# SpsctrumCharacteristicTester.net
KiCad netlist of a schematic drawn in Altium Designer
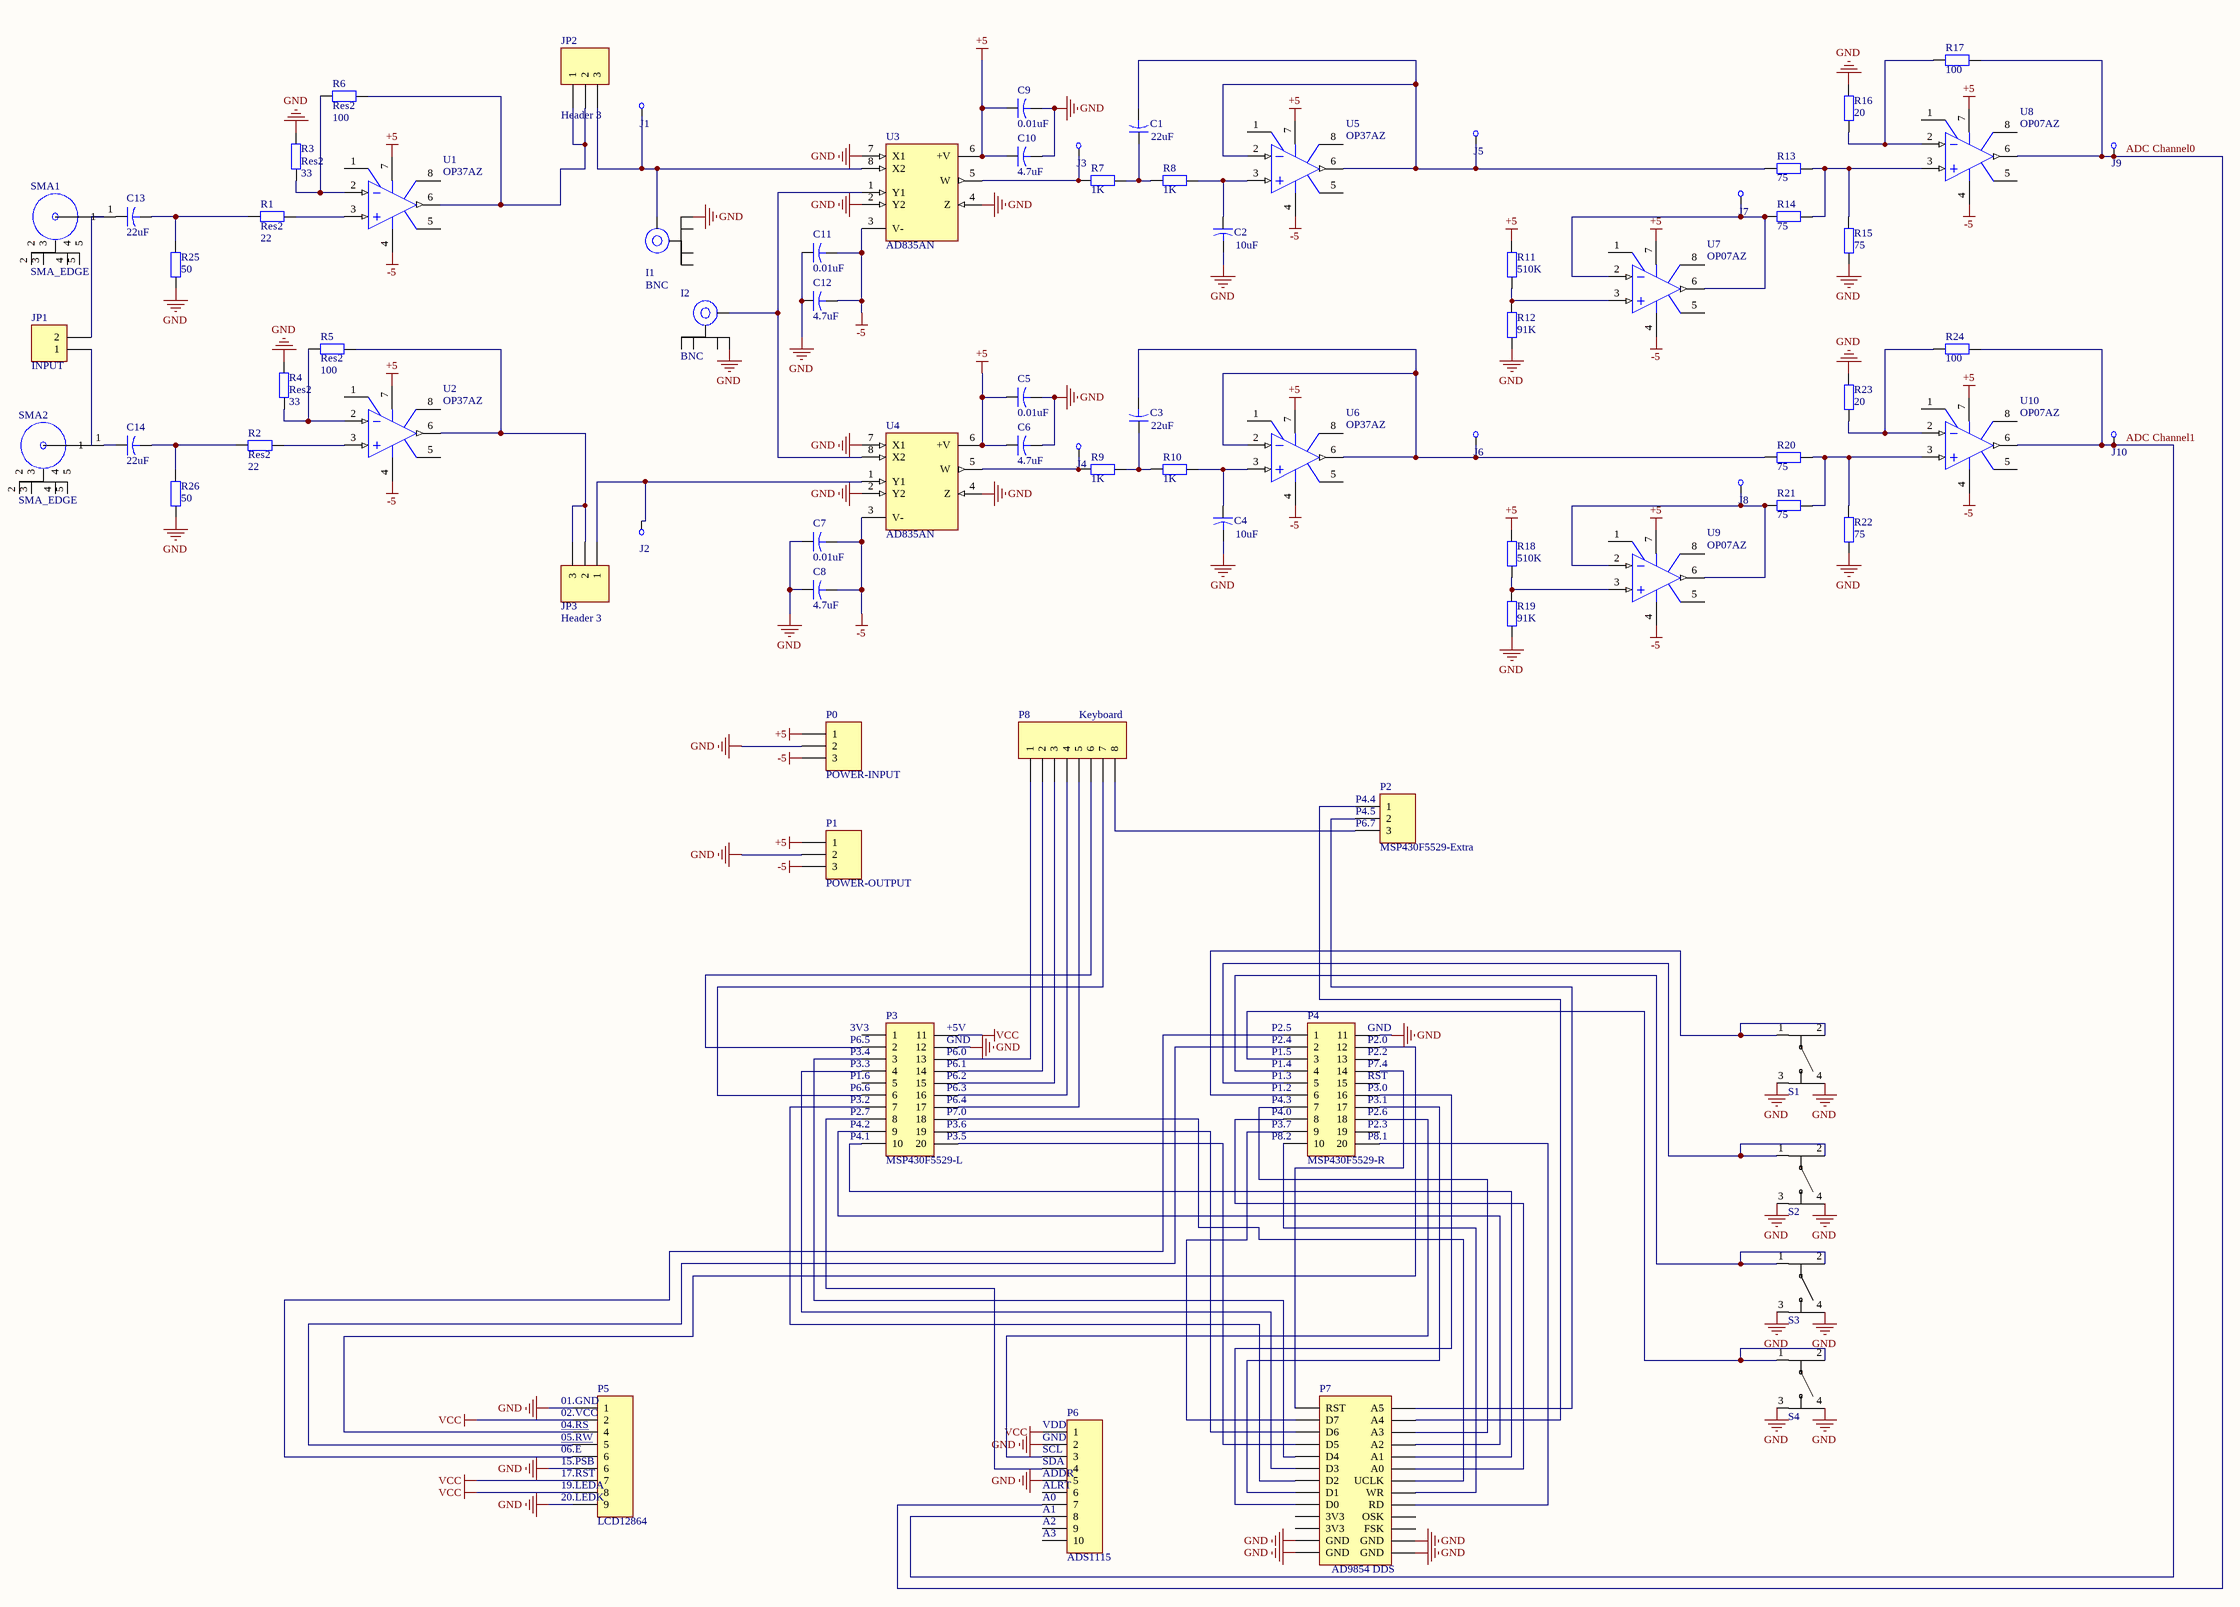
[diagram p0: SpsctrumCharacteristicTester.SchDoc]

(export (version "E")
  (design (tool "Eeschema 10.0.6"))
  (components
    (comp (ref "C1")
      (value "22uF")
      (footprint "CAPR5-4X5")
      (description "Capacitor")
      (fields (field (name "Comment") "Cap2") (field (name "PUBLISHER") "Altium Limited"))
      (libsource (lib "Miscellaneous Devices") (part "Cap2"))
    )
    (comp (ref "C2")
      (value "10uF")
      (footprint "CAPR5-4X5")
      (description "Capacitor")
      (fields (field (name "Comment") "Cap2") (field (name "PUBLISHER") "Altium Limited"))
      (libsource (lib "Miscellaneous Devices") (part "Cap2"))
    )
    (comp (ref "C3")
      (value "22uF")
      (footprint "CAPR5-4X5")
      (description "Capacitor")
      (fields (field (name "Comment") "Cap2") (field (name "PUBLISHER") "Altium Limited"))
      (libsource (lib "Miscellaneous Devices") (part "Cap2"))
    )
    (comp (ref "C4")
      (value "10uF")
      (footprint "CAPR5-4X5")
      (description "Capacitor")
      (fields (field (name "Comment") "Cap2") (field (name "PUBLISHER") "Altium Limited"))
      (libsource (lib "Miscellaneous Devices") (part "Cap2"))
    )
    (comp (ref "C5")
      (value "0.01uF")
      (footprint "CAPR5-4X5")
      (description "Capacitor")
      (fields (field (name "Comment") "Cap2") (field (name "PUBLISHER") "Altium Limited"))
      (libsource (lib "Miscellaneous Devices") (part "Cap2"))
    )
    (comp (ref "C6")
      (value "4.7uF")
      (footprint "CAPR5-4X5")
      (description "Capacitor")
      (fields (field (name "Comment") "Cap2") (field (name "PUBLISHER") "Altium Limited"))
      (libsource (lib "Miscellaneous Devices") (part "Cap2"))
    )
    (comp (ref "C7")
      (value "0.01uF")
      (footprint "CAPR5-4X5")
      (description "Capacitor")
      (fields (field (name "Comment") "Cap2") (field (name "PUBLISHER") "Altium Limited"))
      (libsource (lib "Miscellaneous Devices") (part "Cap2"))
    )
    (comp (ref "C8")
      (value "4.7uF")
      (footprint "CAPR5-4X5")
      (description "Capacitor")
      (fields (field (name "Comment") "Cap2") (field (name "PUBLISHER") "Altium Limited"))
      (libsource (lib "Miscellaneous Devices") (part "Cap2"))
    )
    (comp (ref "C9")
      (value "0.01uF")
      (footprint "CAPR5-4X5")
      (description "Capacitor")
      (fields (field (name "Comment") "Cap2") (field (name "PUBLISHER") "Altium Limited"))
      (libsource (lib "Miscellaneous Devices") (part "Cap2"))
    )
    (comp (ref "C10")
      (value "4.7uF")
      (footprint "CAPR5-4X5")
      (description "Capacitor")
      (fields (field (name "Comment") "Cap2") (field (name "PUBLISHER") "Altium Limited"))
      (libsource (lib "Miscellaneous Devices") (part "Cap2"))
    )
    (comp (ref "C11")
      (value "0.01uF")
      (footprint "CAPR5-4X5")
      (description "Capacitor")
      (fields (field (name "Comment") "Cap2") (field (name "PUBLISHER") "Altium Limited"))
      (libsource (lib "Miscellaneous Devices") (part "Cap2"))
    )
    (comp (ref "C12")
      (value "4.7uF")
      (footprint "CAPR5-4X5")
      (description "Capacitor")
      (fields (field (name "Comment") "Cap2") (field (name "PUBLISHER") "Altium Limited"))
      (libsource (lib "Miscellaneous Devices") (part "Cap2"))
    )
    (comp (ref "C13")
      (value "22uF")
      (footprint "CAPR5-4X5")
      (description "Capacitor")
      (fields (field (name "Comment") "Cap2") (field (name "PUBLISHER") "Altium Limited"))
      (libsource (lib "Miscellaneous Devices") (part "Cap2"))
    )
    (comp (ref "C14")
      (value "22uF")
      (footprint "CAPR5-4X5")
      (description "Capacitor")
      (fields (field (name "Comment") "Cap2") (field (name "PUBLISHER") "Altium Limited"))
      (libsource (lib "Miscellaneous Devices") (part "Cap2"))
    )
    (comp (ref "I1") (value "BNC") (footprint "BNC-KWE") (libsource (lib "BNC") (part "BNC")))
    (comp (ref "I2") (value "BNC") (footprint "BNC-KWE") (libsource (lib "BNC") (part "BNC")))
    (comp (ref "J1")
      (value "CHECK")
      (footprint "CHECK-A")
      (description "测试点")
      (libsource (lib "0MyLib") (part "CHECK"))
    )
    (comp (ref "J2")
      (value "CHECK")
      (footprint "CHECK-A")
      (description "测试点")
      (libsource (lib "0MyLib") (part "CHECK"))
    )
    (comp (ref "J3")
      (value "CHECK")
      (footprint "CHECK-A")
      (description "测试点")
      (libsource (lib "0MyLib") (part "CHECK"))
    )
    (comp (ref "J4")
      (value "CHECK")
      (footprint "CHECK-A")
      (description "测试点")
      (libsource (lib "0MyLib") (part "CHECK"))
    )
    (comp (ref "J5")
      (value "CHECK")
      (footprint "CHECK-A")
      (description "测试点")
      (libsource (lib "0MyLib") (part "CHECK"))
    )
    (comp (ref "J6")
      (value "CHECK")
      (footprint "CHECK-A")
      (description "测试点")
      (libsource (lib "0MyLib") (part "CHECK"))
    )
    (comp (ref "J7")
      (value "CHECK")
      (footprint "CHECK-A")
      (description "测试点")
      (libsource (lib "0MyLib") (part "CHECK"))
    )
    (comp (ref "J8")
      (value "CHECK")
      (footprint "CHECK-A")
      (description "测试点")
      (libsource (lib "0MyLib") (part "CHECK"))
    )
    (comp (ref "J9")
      (value "CHECK")
      (footprint "CHECK-A")
      (description "测试点")
      (libsource (lib "0MyLib") (part "CHECK"))
    )
    (comp (ref "J10")
      (value "CHECK")
      (footprint "CHECK-A")
      (description "测试点")
      (libsource (lib "0MyLib") (part "CHECK"))
    )
    (comp (ref "JP1")
      (value "INPUT")
      (footprint "HDR1X2")
      (description "Header, 2-Pin")
      (fields (field (name "PUBLISHER") "Altium Limited"))
      (libsource (lib "Miscellaneous Connectors") (part "Header 2"))
    )
    (comp (ref "JP2")
      (value "Header 3")
      (footprint "HDR1X3")
      (description "Header, 3-Pin")
      (fields (field (name "PUBLISHER") "Altium Limited"))
      (libsource (lib "") (part "Header 3_1"))
    )
    (comp (ref "JP3")
      (value "Header 3")
      (footprint "HDR1X3")
      (description "Header, 3-Pin")
      (fields (field (name "PUBLISHER") "Altium Limited"))
      (libsource (lib "") (part "Header 3_2"))
    )
    (comp (ref "P0")
      (value "POWER-INPUT")
      (footprint "HDR1X3")
      (description "Header, 3-Pin")
      (fields (field (name "PUBLISHER") "Altium Limited"))
      (libsource (lib "Miscellaneous Connectors") (part "Header 3"))
    )
    (comp (ref "P1")
      (value "POWER-OUTPUT")
      (footprint "HDR1X3")
      (description "Header, 3-Pin")
      (fields (field (name "PUBLISHER") "Altium Limited"))
      (libsource (lib "Miscellaneous Connectors") (part "Header 3"))
    )
    (comp (ref "P2")
      (value "MSP430F5529-Extra")
      (footprint "HDR1X3")
      (description "Header, 3-Pin")
      (fields (field (name "PUBLISHER") "Altium Limited"))
      (libsource (lib "Miscellaneous Connectors") (part "Header 3"))
    )
    (comp (ref "P3")
      (value "MSP430F5529-L")
      (footprint "HDR2X10_CEN")
      (description "Header, 10-Pin, Dual row")
      (fields (field (name "PUBLISHER") "Altium Limited"))
      (libsource (lib "Miscellaneous Connectors") (part "Header 10X2A"))
    )
    (comp (ref "P4")
      (value "MSP430F5529-R")
      (footprint "HDR2X10_CEN")
      (description "Header, 10-Pin, Dual row")
      (fields (field (name "PUBLISHER") "Altium Limited"))
      (libsource (lib "Miscellaneous Connectors") (part "Header 10X2A"))
    )
    (comp (ref "P5")
      (value "LCD12864")
      (footprint "HDR1X9")
      (description "Header, 9-Pin")
      (fields (field (name "PUBLISHER") "Altium Limited"))
      (libsource (lib "Miscellaneous Connectors") (part "Header 9"))
    )
    (comp (ref "P6")
      (value "ADS1115")
      (footprint "HDR1X10")
      (description "Header, 10-Pin")
      (fields (field (name "PUBLISHER") "Altium Limited"))
      (libsource (lib "Miscellaneous Connectors") (part "Header 10"))
    )
    (comp (ref "P7")
      (value "~")
      (footprint "IDC-26")
      (libsource (lib "AD9854 Connector") (part "AD9854 DDS"))
    )
    (comp (ref "P8")
      (value "Keyboard")
      (footprint "HDR1X8")
      (description "Header, 8-Pin")
      (fields (field (name "PUBLISHER") "Altium Limited"))
      (libsource (lib "Miscellaneous Connectors") (part "Header 8"))
    )
    (comp (ref "R1")
      (value "Res2")
      (footprint "AXIAL-0.4")
      (description "Resistor")
      (fields (field (name "ALTIUM_VALUE") "22") (field (name "PUBLISHER") "Altium Limited"))
      (libsource (lib "") (part "Res2_1"))
    )
    (comp (ref "R2")
      (value "Res2")
      (footprint "AXIAL-0.4")
      (description "Resistor")
      (fields (field (name "ALTIUM_VALUE") "22") (field (name "PUBLISHER") "Altium Limited"))
      (libsource (lib "") (part "Res2_1"))
    )
    (comp (ref "R3")
      (value "Res2")
      (footprint "AXIAL-0.4")
      (description "Resistor")
      (fields (field (name "ALTIUM_VALUE") "33") (field (name "PUBLISHER") "Altium Limited"))
      (libsource (lib "Miscellaneous Devices") (part "Res2"))
    )
    (comp (ref "R4")
      (value "Res2")
      (footprint "AXIAL-0.4")
      (description "Resistor")
      (fields (field (name "ALTIUM_VALUE") "33") (field (name "PUBLISHER") "Altium Limited"))
      (libsource (lib "Miscellaneous Devices") (part "Res2"))
    )
    (comp (ref "R5")
      (value "Res2")
      (footprint "AXIAL-0.4")
      (description "Resistor")
      (fields (field (name "ALTIUM_VALUE") "100") (field (name "PUBLISHER") "Altium Limited"))
      (libsource (lib "") (part "Res2_2"))
    )
    (comp (ref "R6")
      (value "Res2")
      (footprint "AXIAL-0.4")
      (description "Resistor")
      (fields (field (name "ALTIUM_VALUE") "100") (field (name "PUBLISHER") "Altium Limited"))
      (libsource (lib "") (part "Res2_2"))
    )
    (comp (ref "R7")
      (value "1K")
      (footprint "AXIAL-0.4")
      (description "Resistor")
      (fields (field (name "Comment") "Res2") (field (name "PUBLISHER") "Altium Limited"))
      (libsource (lib "") (part "Res2_1"))
    )
    (comp (ref "R8")
      (value "1K")
      (footprint "AXIAL-0.4")
      (description "Resistor")
      (fields (field (name "Comment") "Res2") (field (name "PUBLISHER") "Altium Limited"))
      (libsource (lib "") (part "Res2_1"))
    )
    (comp (ref "R9")
      (value "1K")
      (footprint "AXIAL-0.4")
      (description "Resistor")
      (fields (field (name "Comment") "Res2") (field (name "PUBLISHER") "Altium Limited"))
      (libsource (lib "") (part "Res2_1"))
    )
    (comp (ref "R10")
      (value "1K")
      (footprint "AXIAL-0.4")
      (description "Resistor")
      (fields (field (name "Comment") "Res2") (field (name "PUBLISHER") "Altium Limited"))
      (libsource (lib "") (part "Res2_1"))
    )
    (comp (ref "R11")
      (value "510K")
      (footprint "AXIAL-0.4")
      (description "Resistor")
      (fields (field (name "Comment") "Res2") (field (name "PUBLISHER") "Altium Limited"))
      (libsource (lib "Miscellaneous Devices") (part "Res2"))
    )
    (comp (ref "R12")
      (value "91K")
      (footprint "AXIAL-0.4")
      (description "Resistor")
      (fields (field (name "Comment") "Res2") (field (name "PUBLISHER") "Altium Limited"))
      (libsource (lib "Miscellaneous Devices") (part "Res2"))
    )
    (comp (ref "R13")
      (value "75")
      (footprint "AXIAL-0.4")
      (description "Resistor")
      (fields (field (name "Comment") "Res2") (field (name "PUBLISHER") "Altium Limited"))
      (libsource (lib "") (part "Res2_1"))
    )
    (comp (ref "R14")
      (value "75")
      (footprint "AXIAL-0.4")
      (description "Resistor")
      (fields (field (name "Comment") "Res2") (field (name "PUBLISHER") "Altium Limited"))
      (libsource (lib "") (part "Res2_1"))
    )
    (comp (ref "R15")
      (value "75")
      (footprint "AXIAL-0.4")
      (description "Resistor")
      (fields (field (name "Comment") "Res2") (field (name "PUBLISHER") "Altium Limited"))
      (libsource (lib "Miscellaneous Devices") (part "Res2"))
    )
    (comp (ref "R16")
      (value "20")
      (footprint "AXIAL-0.4")
      (description "Resistor")
      (fields (field (name "Comment") "Res2") (field (name "PUBLISHER") "Altium Limited"))
      (libsource (lib "") (part "Res2_3"))
    )
    (comp (ref "R17")
      (value "100")
      (footprint "AXIAL-0.4")
      (description "Resistor")
      (fields (field (name "Comment") "Res2") (field (name "PUBLISHER") "Altium Limited"))
      (libsource (lib "") (part "Res2_1"))
    )
    (comp (ref "R18")
      (value "510K")
      (footprint "AXIAL-0.4")
      (description "Resistor")
      (fields (field (name "Comment") "Res2") (field (name "PUBLISHER") "Altium Limited"))
      (libsource (lib "Miscellaneous Devices") (part "Res2"))
    )
    (comp (ref "R19")
      (value "91K")
      (footprint "AXIAL-0.4")
      (description "Resistor")
      (fields (field (name "Comment") "Res2") (field (name "PUBLISHER") "Altium Limited"))
      (libsource (lib "Miscellaneous Devices") (part "Res2"))
    )
    (comp (ref "R20")
      (value "75")
      (footprint "AXIAL-0.4")
      (description "Resistor")
      (fields (field (name "Comment") "Res2") (field (name "PUBLISHER") "Altium Limited"))
      (libsource (lib "") (part "Res2_1"))
    )
    (comp (ref "R21")
      (value "75")
      (footprint "AXIAL-0.4")
      (description "Resistor")
      (fields (field (name "Comment") "Res2") (field (name "PUBLISHER") "Altium Limited"))
      (libsource (lib "") (part "Res2_1"))
    )
    (comp (ref "R22")
      (value "75")
      (footprint "AXIAL-0.4")
      (description "Resistor")
      (fields (field (name "Comment") "Res2") (field (name "PUBLISHER") "Altium Limited"))
      (libsource (lib "Miscellaneous Devices") (part "Res2"))
    )
    (comp (ref "R23")
      (value "20")
      (footprint "AXIAL-0.4")
      (description "Resistor")
      (fields (field (name "Comment") "Res2") (field (name "PUBLISHER") "Altium Limited"))
      (libsource (lib "") (part "Res2_3"))
    )
    (comp (ref "R24")
      (value "100")
      (footprint "AXIAL-0.4")
      (description "Resistor")
      (fields (field (name "Comment") "Res2") (field (name "PUBLISHER") "Altium Limited"))
      (libsource (lib "") (part "Res2_1"))
    )
    (comp (ref "R25")
      (value "50")
      (footprint "AXIAL-0.4")
      (description "Resistor")
      (fields (field (name "Comment") "Res2") (field (name "PUBLISHER") "Altium Limited"))
      (libsource (lib "Miscellaneous Devices") (part "Res2"))
    )
    (comp (ref "R26")
      (value "50")
      (footprint "AXIAL-0.4")
      (description "Resistor")
      (fields (field (name "Comment") "Res2") (field (name "PUBLISHER") "Altium Limited"))
      (libsource (lib "Miscellaneous Devices") (part "Res2"))
    )
    (comp (ref "S1") (value "6*6 微动开关") (footprint "6*6微动开关") (libsource (lib "Siwitches") (part "6*6 微动开关")))
    (comp (ref "S2") (value "6*6 微动开关") (footprint "6*6微动开关") (libsource (lib "Siwitches") (part "6*6 微动开关")))
    (comp (ref "S3") (value "6*6 微动开关") (footprint "6*6微动开关") (libsource (lib "Siwitches") (part "6*6 微动开关")))
    (comp (ref "S4") (value "6*6 微动开关") (footprint "6*6微动开关") (libsource (lib "Siwitches") (part "6*6 微动开关")))
    (comp (ref "SMA1")
      (value "SMA_EDGE")
      (footprint "SMA_EDGE")
      (description "SMA接口")
      (libsource (lib "SMA") (part "SMA_EDGE"))
    )
    (comp (ref "SMA2")
      (value "SMA_EDGE")
      (footprint "SMA_EDGE")
      (description "SMA接口")
      (libsource (lib "SMA") (part "SMA_EDGE"))
    )
    (comp (ref "U1")
      (value "OP37AZ")
      (footprint "Q-8")
      (description "Low-Noise, Precision, High-Speed Operational Amplifier (Avcl >= 5)")
      (fields (field (name "PUBLISHER") "Altium Limited"))
      (libsource (lib "AD Operational Amplifier") (part "OP37AZ"))
    )
    (comp (ref "U2")
      (value "OP37AZ")
      (footprint "Q-8")
      (description "Low-Noise, Precision, High-Speed Operational Amplifier (Avcl >= 5)")
      (fields (field (name "PUBLISHER") "Altium Limited"))
      (libsource (lib "AD Operational Amplifier") (part "OP37AZ"))
    )
    (comp (ref "U3")
      (value "AD835AN")
      (footprint "N-8_A")
      (description "250MHz, Voltage Output 4-Quadrant Multiplier")
      (fields (field (name "PUBLISHER") "Altium Limited"))
      (libsource (lib "AD Analog Multiplier Divider") (part "AD835AN"))
    )
    (comp (ref "U4")
      (value "AD835AN")
      (footprint "N-8_A")
      (description "250MHz, Voltage Output 4-Quadrant Multiplier")
      (fields (field (name "PUBLISHER") "Altium Limited"))
      (libsource (lib "AD Analog Multiplier Divider") (part "AD835AN"))
    )
    (comp (ref "U5")
      (value "OP37AZ")
      (footprint "Q-8")
      (description "Low-Noise, Precision, High-Speed Operational Amplifier (Avcl >= 5)")
      (fields (field (name "PUBLISHER") "Altium Limited"))
      (libsource (lib "AD Operational Amplifier") (part "OP37AZ"))
    )
    (comp (ref "U6")
      (value "OP37AZ")
      (footprint "Q-8")
      (description "Low-Noise, Precision, High-Speed Operational Amplifier (Avcl >= 5)")
      (fields (field (name "PUBLISHER") "Altium Limited"))
      (libsource (lib "AD Operational Amplifier") (part "OP37AZ"))
    )
    (comp (ref "U7")
      (value "OP07AZ")
      (footprint "Q-8")
      (description "Ultra-Low Offset Voltage Operational Amplifier")
      (fields (field (name "PUBLISHER") "Altium Limited"))
      (libsource (lib "AD Operational Amplifier") (part "OP07AZ"))
    )
    (comp (ref "U8")
      (value "OP07AZ")
      (footprint "Q-8")
      (description "Ultra-Low Offset Voltage Operational Amplifier")
      (fields (field (name "PUBLISHER") "Altium Limited"))
      (libsource (lib "AD Operational Amplifier") (part "OP07AZ"))
    )
    (comp (ref "U9")
      (value "OP07AZ")
      (footprint "Q-8")
      (description "Ultra-Low Offset Voltage Operational Amplifier")
      (fields (field (name "PUBLISHER") "Altium Limited"))
      (libsource (lib "AD Operational Amplifier") (part "OP07AZ"))
    )
    (comp (ref "U10")
      (value "OP07AZ")
      (footprint "Q-8")
      (description "Ultra-Low Offset Voltage Operational Amplifier")
      (fields (field (name "PUBLISHER") "Altium Limited"))
      (libsource (lib "AD Operational Amplifier") (part "OP07AZ"))
    )
  )
  (nets
    (net (code "1") (name "+5") (class "Default")
      (node (ref "C10") (pin "1") (pinfunction "1_1") (pintype "passive"))
      (node (ref "C5") (pin "1") (pinfunction "1_1") (pintype "passive"))
      (node (ref "C6") (pin "1") (pinfunction "1_1") (pintype "passive"))
      (node (ref "C9") (pin "1") (pinfunction "1_1") (pintype "passive"))
      (node (ref "P0") (pin "1") (pinfunction "1_1") (pintype "passive"))
      (node (ref "P1") (pin "1") (pinfunction "1_1") (pintype "passive"))
      (node (ref "R11") (pin "2") (pinfunction "2_2") (pintype "passive"))
      (node (ref "R18") (pin "2") (pinfunction "2_2") (pintype "passive"))
      (node (ref "U1") (pin "7") (pinfunction "V+_7") (pintype "power_in"))
      (node (ref "U10") (pin "7") (pinfunction "V+_7") (pintype "power_in"))
      (node (ref "U2") (pin "7") (pinfunction "V+_7") (pintype "power_in"))
      (node (ref "U3") (pin "6") (pinfunction "+V_6") (pintype "power_in"))
      (node (ref "U4") (pin "6") (pinfunction "+V_6") (pintype "power_in"))
      (node (ref "U5") (pin "7") (pinfunction "V+_7") (pintype "power_in"))
      (node (ref "U6") (pin "7") (pinfunction "V+_7") (pintype "power_in"))
      (node (ref "U7") (pin "7") (pinfunction "V+_7") (pintype "power_in"))
      (node (ref "U8") (pin "7") (pinfunction "V+_7") (pintype "power_in"))
      (node (ref "U9") (pin "7") (pinfunction "V+_7") (pintype "power_in"))
    )
    (net (code "2") (name "-5") (class "Default")
      (node (ref "C11") (pin "2") (pinfunction "2_2") (pintype "passive"))
      (node (ref "C12") (pin "2") (pinfunction "2_2") (pintype "passive"))
      (node (ref "C7") (pin "2") (pinfunction "2_2") (pintype "passive"))
      (node (ref "C8") (pin "2") (pinfunction "2_2") (pintype "passive"))
      (node (ref "P0") (pin "3") (pinfunction "3_3") (pintype "passive"))
      (node (ref "P1") (pin "3") (pinfunction "3_3") (pintype "passive"))
      (node (ref "U1") (pin "4") (pinfunction "V-_4") (pintype "power_in"))
      (node (ref "U10") (pin "4") (pinfunction "V-_4") (pintype "power_in"))
      (node (ref "U2") (pin "4") (pinfunction "V-_4") (pintype "power_in"))
      (node (ref "U3") (pin "3") (pinfunction "V-_3") (pintype "power_in"))
      (node (ref "U4") (pin "3") (pinfunction "V-_3") (pintype "power_in"))
      (node (ref "U5") (pin "4") (pinfunction "V-_4") (pintype "power_in"))
      (node (ref "U6") (pin "4") (pinfunction "V-_4") (pintype "power_in"))
      (node (ref "U7") (pin "4") (pinfunction "V-_4") (pintype "power_in"))
      (node (ref "U8") (pin "4") (pinfunction "V-_4") (pintype "power_in"))
      (node (ref "U9") (pin "4") (pinfunction "V-_4") (pintype "power_in"))
    )
    (net (code "3") (name "/ADC Channel0") (class "Default")
      (node (ref "J9") (pin "1") (pinfunction "1_1") (pintype "passive"))
      (node (ref "P6") (pin "7") (pinfunction "7_7") (pintype "passive"))
      (node (ref "R17") (pin "2") (pinfunction "2_2") (pintype "passive"))
      (node (ref "U8") (pin "6") (pinfunction "OUT_6") (pintype "output"))
    )
    (net (code "4") (name "/ADC Channel1") (class "Default")
      (node (ref "J10") (pin "1") (pinfunction "1_1") (pintype "passive"))
      (node (ref "P6") (pin "8") (pinfunction "8_8") (pintype "passive"))
      (node (ref "R24") (pin "2") (pinfunction "2_2") (pintype "passive"))
      (node (ref "U10") (pin "6") (pinfunction "OUT_6") (pintype "output"))
    )
    (net (code "5") (name "GND") (class "Default")
      (node (ref "C10") (pin "2") (pinfunction "2_2") (pintype "passive"))
      (node (ref "C11") (pin "1") (pinfunction "1_1") (pintype "passive"))
      (node (ref "C12") (pin "1") (pinfunction "1_1") (pintype "passive"))
      (node (ref "C2") (pin "2") (pinfunction "2_2") (pintype "passive"))
      (node (ref "C4") (pin "2") (pinfunction "2_2") (pintype "passive"))
      (node (ref "C5") (pin "2") (pinfunction "2_2") (pintype "passive"))
      (node (ref "C6") (pin "2") (pinfunction "2_2") (pintype "passive"))
      (node (ref "C7") (pin "1") (pinfunction "1_1") (pintype "passive"))
      (node (ref "C8") (pin "1") (pinfunction "1_1") (pintype "passive"))
      (node (ref "C9") (pin "2") (pinfunction "2_2") (pintype "passive"))
      (node (ref "I1") (pin "5") (pinfunction "5_5") (pintype "passive"))
      (node (ref "I2") (pin "5") (pinfunction "5_5") (pintype "passive"))
      (node (ref "P0") (pin "2") (pinfunction "2_2") (pintype "passive"))
      (node (ref "P1") (pin "2") (pinfunction "2_2") (pintype "passive"))
      (node (ref "P3") (pin "12") (pinfunction "12_12") (pintype "passive"))
      (node (ref "P4") (pin "11") (pinfunction "11_11") (pintype "passive"))
      (node (ref "P5") (pin "1") (pinfunction "1_1") (pintype "passive"))
      (node (ref "P5") (pin "6") (pinfunction "6_6") (pintype "passive"))
      (node (ref "P5") (pin "9") (pinfunction "9_9") (pintype "passive"))
      (node (ref "P6") (pin "2") (pinfunction "2_2") (pintype "passive"))
      (node (ref "P6") (pin "5") (pinfunction "5_5") (pintype "passive"))
      (node (ref "P7") (pin "23") (pinfunction "GND_23") (pintype "passive"))
      (node (ref "P7") (pin "24") (pinfunction "GND_24") (pintype "passive"))
      (node (ref "P7") (pin "25") (pinfunction "GND_25") (pintype "passive"))
      (node (ref "P7") (pin "26") (pinfunction "GND_26") (pintype "passive"))
      (node (ref "R12") (pin "1") (pinfunction "1_1") (pintype "passive"))
      (node (ref "R15") (pin "1") (pinfunction "1_1") (pintype "passive"))
      (node (ref "R16") (pin "1") (pinfunction "1_1") (pintype "passive"))
      (node (ref "R19") (pin "1") (pinfunction "1_1") (pintype "passive"))
      (node (ref "R22") (pin "1") (pinfunction "1_1") (pintype "passive"))
      (node (ref "R23") (pin "1") (pinfunction "1_1") (pintype "passive"))
      (node (ref "R25") (pin "1") (pinfunction "1_1") (pintype "passive"))
      (node (ref "R26") (pin "1") (pinfunction "1_1") (pintype "passive"))
      (node (ref "R3") (pin "2") (pinfunction "2_2") (pintype "passive"))
      (node (ref "R4") (pin "2") (pinfunction "2_2") (pintype "passive"))
      (node (ref "S1") (pin "3") (pintype "passive"))
      (node (ref "S1") (pin "4") (pinfunction "4_4") (pintype "passive"))
      (node (ref "S2") (pin "3") (pintype "passive"))
      (node (ref "S2") (pin "4") (pinfunction "4_4") (pintype "passive"))
      (node (ref "S3") (pin "3") (pintype "passive"))
      (node (ref "S3") (pin "4") (pinfunction "4_4") (pintype "passive"))
      (node (ref "S4") (pin "3") (pintype "passive"))
      (node (ref "S4") (pin "4") (pinfunction "4_4") (pintype "passive"))
      (node (ref "U3") (pin "2") (pinfunction "Y2_2") (pintype "input"))
      (node (ref "U3") (pin "4") (pinfunction "Z_4") (pintype "input"))
      (node (ref "U3") (pin "7") (pinfunction "X1_7") (pintype "input"))
      (node (ref "U4") (pin "2") (pinfunction "Y2_2") (pintype "input"))
      (node (ref "U4") (pin "4") (pinfunction "Z_4") (pintype "input"))
      (node (ref "U4") (pin "7") (pinfunction "X1_7") (pintype "input"))
    )
    (net (code "6") (name "Net-(C1-Pad1)") (class "Default")
      (node (ref "C1") (pin "1") (pinfunction "1_1") (pintype "passive"))
      (node (ref "R7") (pin "2") (pinfunction "2_2") (pintype "passive"))
      (node (ref "R8") (pin "1") (pinfunction "1_1") (pintype "passive"))
    )
    (net (code "7") (name "Net-(C3-Pad1)") (class "Default")
      (node (ref "C3") (pin "1") (pinfunction "1_1") (pintype "passive"))
      (node (ref "R10") (pin "1") (pinfunction "1_1") (pintype "passive"))
      (node (ref "R9") (pin "2") (pinfunction "2_2") (pintype "passive"))
    )
    (net (code "8") (name "Net-(C13-Pad1)") (class "Default")
      (node (ref "C13") (pin "1") (pinfunction "1_1") (pintype "passive"))
      (node (ref "SMA1") (pin "1") (pinfunction "1_1") (pintype "passive"))
    )
    (net (code "9") (name "Net-(C13-Pad2)") (class "Default")
      (node (ref "C13") (pin "2") (pinfunction "2_2") (pintype "passive"))
      (node (ref "R1") (pin "1") (pinfunction "1_1") (pintype "passive"))
      (node (ref "R25") (pin "2") (pinfunction "2_2") (pintype "passive"))
    )
    (net (code "10") (name "Net-(C14-Pad1)") (class "Default")
      (node (ref "C14") (pin "1") (pinfunction "1_1") (pintype "passive"))
      (node (ref "SMA2") (pin "1") (pinfunction "1_1") (pintype "passive"))
    )
    (net (code "11") (name "Net-(C14-Pad2)") (class "Default")
      (node (ref "C14") (pin "2") (pinfunction "2_2") (pintype "passive"))
      (node (ref "R2") (pin "1") (pinfunction "1_1") (pintype "passive"))
      (node (ref "R26") (pin "2") (pinfunction "2_2") (pintype "passive"))
    )
    (net (code "12") (name "Net-(P2-Pad3)") (class "Default")
      (node (ref "P2") (pin "3") (pinfunction "3_3") (pintype "passive"))
      (node (ref "P8") (pin "8") (pinfunction "8_8") (pintype "passive"))
    )
    (net (code "13") (name "Net-(P3-Pad2)") (class "Default")
      (node (ref "P3") (pin "2") (pinfunction "2_2") (pintype "passive"))
      (node (ref "P8") (pin "6") (pinfunction "6_6") (pintype "passive"))
    )
    (net (code "14") (name "Net-(P3-Pad6)") (class "Default")
      (node (ref "P3") (pin "6") (pinfunction "6_6") (pintype "passive"))
      (node (ref "P8") (pin "7") (pinfunction "7_7") (pintype "passive"))
    )
    (net (code "15") (name "Net-(P3-Pad8)") (class "Default")
      (node (ref "P3") (pin "8") (pinfunction "8_8") (pintype "passive"))
      (node (ref "P6") (pin "4") (pinfunction "4_4") (pintype "passive"))
    )
    (net (code "16") (name "Net-(P3-Pad13)") (class "Default")
      (node (ref "P3") (pin "13") (pinfunction "13_13") (pintype "passive"))
      (node (ref "P8") (pin "1") (pinfunction "1_1") (pintype "passive"))
    )
    (net (code "17") (name "Net-(P3-Pad14)") (class "Default")
      (node (ref "P3") (pin "14") (pinfunction "14_14") (pintype "passive"))
      (node (ref "P8") (pin "2") (pinfunction "2_2") (pintype "passive"))
    )
    (net (code "18") (name "Net-(P3-Pad15)") (class "Default")
      (node (ref "P3") (pin "15") (pinfunction "15_15") (pintype "passive"))
      (node (ref "P8") (pin "3") (pinfunction "3_3") (pintype "passive"))
    )
    (net (code "19") (name "Net-(P3-Pad16)") (class "Default")
      (node (ref "P3") (pin "16") (pinfunction "16_16") (pintype "passive"))
      (node (ref "P8") (pin "4") (pinfunction "4_4") (pintype "passive"))
    )
    (net (code "20") (name "Net-(P3-Pad17)") (class "Default")
      (node (ref "P3") (pin "17") (pinfunction "17_17") (pintype "passive"))
      (node (ref "P8") (pin "5") (pinfunction "5_5") (pintype "passive"))
    )
    (net (code "21") (name "Net-(P4-Pad1)") (class "Default")
      (node (ref "P4") (pin "1") (pinfunction "1_1") (pintype "passive"))
      (node (ref "P5") (pin "6") (pinfunction "6_6") (pintype "passive"))
    )
    (net (code "22") (name "Net-(P4-Pad2)") (class "Default")
      (node (ref "P4") (pin "2") (pinfunction "2_2") (pintype "passive"))
      (node (ref "P5") (pin "5") (pinfunction "5_5") (pintype "passive"))
    )
    (net (code "23") (name "Net-(P4-Pad3)") (class "Default")
      (node (ref "P4") (pin "3") (pinfunction "3_3") (pintype "passive"))
      (node (ref "S4") (pin "1") (pinfunction "1_1") (pintype "passive"))
      (node (ref "S4") (pin "2") (pinfunction "2_2") (pintype "passive"))
    )
    (net (code "24") (name "Net-(P4-Pad4)") (class "Default")
      (node (ref "P4") (pin "4") (pinfunction "4_4") (pintype "passive"))
      (node (ref "S3") (pin "1") (pinfunction "1_1") (pintype "passive"))
      (node (ref "S3") (pin "2") (pinfunction "2_2") (pintype "passive"))
    )
    (net (code "25") (name "Net-(P4-Pad5)") (class "Default")
      (node (ref "P4") (pin "5") (pinfunction "5_5") (pintype "passive"))
      (node (ref "S2") (pin "1") (pinfunction "1_1") (pintype "passive"))
      (node (ref "S2") (pin "2") (pinfunction "2_2") (pintype "passive"))
    )
    (net (code "26") (name "Net-(P4-Pad6)") (class "Default")
      (node (ref "P4") (pin "6") (pinfunction "6_6") (pintype "passive"))
      (node (ref "S1") (pin "1") (pinfunction "1_1") (pintype "passive"))
      (node (ref "S1") (pin "2") (pinfunction "2_2") (pintype "passive"))
    )
    (net (code "27") (name "Net-(P4-Pad12)") (class "Default")
      (node (ref "P4") (pin "12") (pinfunction "12_12") (pintype "passive"))
      (node (ref "P5") (pin "4") (pinfunction "4_4") (pintype "passive"))
    )
    (net (code "28") (name "Net-(P4-Pad18)") (class "Default")
      (node (ref "P4") (pin "18") (pinfunction "18_18") (pintype "passive"))
      (node (ref "P6") (pin "3") (pinfunction "3_3") (pintype "passive"))
    )
    (net (code "29") (name "Net-(P7-A0)") (class "Default")
      (node (ref "P4") (pin "8") (pinfunction "8_8") (pintype "passive"))
      (node (ref "P7") (pin "12") (pinfunction "A0_12") (pintype "passive"))
    )
    (net (code "30") (name "Net-(P7-A1)") (class "Default")
      (node (ref "P3") (pin "10") (pinfunction "10_10") (pintype "passive"))
      (node (ref "P7") (pin "10") (pinfunction "A1_10") (pintype "passive"))
    )
    (net (code "31") (name "Net-(P7-A2)") (class "Default")
      (node (ref "P3") (pin "9") (pinfunction "9_9") (pintype "passive"))
      (node (ref "P7") (pin "8") (pinfunction "A2_8") (pintype "passive"))
    )
    (net (code "32") (name "Net-(P7-A3)") (class "Default")
      (node (ref "P4") (pin "7") (pinfunction "7_7") (pintype "passive"))
      (node (ref "P7") (pin "6") (pinfunction "A3_6") (pintype "passive"))
    )
    (net (code "33") (name "Net-(P7-A4)") (class "Default")
      (node (ref "P2") (pin "1") (pinfunction "1_1") (pintype "passive"))
      (node (ref "P7") (pin "4") (pinfunction "A4_4") (pintype "passive"))
    )
    (net (code "34") (name "Net-(P7-A5)") (class "Default")
      (node (ref "P2") (pin "2") (pinfunction "2_2") (pintype "passive"))
      (node (ref "P7") (pin "2") (pinfunction "A5_2") (pintype "passive"))
    )
    (net (code "35") (name "Net-(P7-D0)") (class "Default")
      (node (ref "P4") (pin "16") (pinfunction "16_16") (pintype "passive"))
      (node (ref "P7") (pin "17") (pinfunction "D0_17") (pintype "passive"))
    )
    (net (code "36") (name "Net-(P7-D1)") (class "Default")
      (node (ref "P4") (pin "17") (pinfunction "17_17") (pintype "passive"))
      (node (ref "P7") (pin "15") (pinfunction "D1_15") (pintype "passive"))
    )
    (net (code "37") (name "Net-(P7-D2)") (class "Default")
      (node (ref "P3") (pin "7") (pinfunction "7_7") (pintype "passive"))
      (node (ref "P7") (pin "13") (pinfunction "D2_13") (pintype "passive"))
    )
    (net (code "38") (name "Net-(P7-D3)") (class "Default")
      (node (ref "P3") (pin "4") (pinfunction "4_4") (pintype "passive"))
      (node (ref "P7") (pin "11") (pinfunction "D3_11") (pintype "passive"))
    )
    (net (code "39") (name "Net-(P7-D4)") (class "Default")
      (node (ref "P3") (pin "3") (pinfunction "3_3") (pintype "passive"))
      (node (ref "P7") (pin "9") (pinfunction "D4_9") (pintype "passive"))
    )
    (net (code "40") (name "Net-(P7-D5)") (class "Default")
      (node (ref "P3") (pin "20") (pinfunction "20_20") (pintype "passive"))
      (node (ref "P7") (pin "7") (pinfunction "D5_7") (pintype "passive"))
    )
    (net (code "41") (name "Net-(P7-D6)") (class "Default")
      (node (ref "P3") (pin "19") (pinfunction "19_19") (pintype "passive"))
      (node (ref "P7") (pin "5") (pinfunction "D6_5") (pintype "passive"))
    )
    (net (code "42") (name "Net-(P7-D7)") (class "Default")
      (node (ref "P4") (pin "9") (pinfunction "9_9") (pintype "passive"))
      (node (ref "P7") (pin "3") (pinfunction "D7_3") (pintype "passive"))
    )
    (net (code "43") (name "Net-(P7-RD)") (class "Default")
      (node (ref "P4") (pin "20") (pinfunction "20_20") (pintype "passive"))
      (node (ref "P7") (pin "18") (pinfunction "RD_18") (pintype "passive"))
    )
    (net (code "44") (name "Net-(P7-RST)") (class "Default")
      (node (ref "P4") (pin "14") (pinfunction "14_14") (pintype "passive"))
      (node (ref "P7") (pin "1") (pinfunction "RST_1") (pintype "passive"))
    )
    (net (code "45") (name "Net-(P7-UCLK)") (class "Default")
      (node (ref "P3") (pin "18") (pinfunction "18_18") (pintype "passive"))
      (node (ref "P7") (pin "14") (pinfunction "UCLK_14") (pintype "passive"))
    )
    (net (code "46") (name "Net-(P7-WR)") (class "Default")
      (node (ref "P4") (pin "10") (pinfunction "10_10") (pintype "passive"))
      (node (ref "P7") (pin "16") (pinfunction "WR_16") (pintype "passive"))
    )
    (net (code "47") (name "Net-(U1-IN+)") (class "Default")
      (node (ref "R1") (pin "2") (pinfunction "2_2") (pintype "passive"))
      (node (ref "U1") (pin "3") (pinfunction "IN+_3") (pintype "input"))
    )
    (net (code "48") (name "Net-(U1-IN-)") (class "Default")
      (node (ref "R3") (pin "1") (pinfunction "1_1") (pintype "passive"))
      (node (ref "R6") (pin "2") (pinfunction "2_2") (pintype "passive"))
      (node (ref "U1") (pin "2") (pinfunction "IN-_2") (pintype "input"))
    )
    (net (code "49") (name "Net-(U1-OUT)") (class "Default")
      (node (ref "JP2") (pin "1") (pinfunction "1_1") (pintype "passive"))
      (node (ref "JP2") (pin "2") (pinfunction "2_2") (pintype "passive"))
      (node (ref "R6") (pin "1") (pinfunction "1_1") (pintype "passive"))
      (node (ref "U1") (pin "6") (pinfunction "OUT_6") (pintype "output"))
    )
    (net (code "50") (name "Net-(U2-IN+)") (class "Default")
      (node (ref "R2") (pin "2") (pinfunction "2_2") (pintype "passive"))
      (node (ref "U2") (pin "3") (pinfunction "IN+_3") (pintype "input"))
    )
    (net (code "51") (name "Net-(U2-IN-)") (class "Default")
      (node (ref "R4") (pin "1") (pinfunction "1_1") (pintype "passive"))
      (node (ref "R5") (pin "2") (pinfunction "2_2") (pintype "passive"))
      (node (ref "U2") (pin "2") (pinfunction "IN-_2") (pintype "input"))
    )
    (net (code "52") (name "Net-(U2-OUT)") (class "Default")
      (node (ref "JP3") (pin "2") (pinfunction "2_2") (pintype "passive"))
      (node (ref "JP3") (pin "3") (pinfunction "3_3") (pintype "passive"))
      (node (ref "R5") (pin "1") (pinfunction "1_1") (pintype "passive"))
      (node (ref "U2") (pin "6") (pinfunction "OUT_6") (pintype "output"))
    )
    (net (code "53") (name "Net-(U3-W)") (class "Default")
      (node (ref "J3") (pin "1") (pinfunction "1_1") (pintype "passive"))
      (node (ref "R7") (pin "1") (pinfunction "1_1") (pintype "passive"))
      (node (ref "U3") (pin "5") (pinfunction "W_5") (pintype "output"))
    )
    (net (code "54") (name "Net-(U3-X2)") (class "Default")
      (node (ref "I1") (pin "1") (pinfunction "1_1") (pintype "passive"))
      (node (ref "J1") (pin "1") (pinfunction "1_1") (pintype "passive"))
      (node (ref "JP2") (pin "3") (pinfunction "3_3") (pintype "passive"))
      (node (ref "U3") (pin "8") (pinfunction "X2_8") (pintype "input"))
    )
    (net (code "55") (name "Net-(U3-Y1)") (class "Default")
      (node (ref "I2") (pin "1") (pinfunction "1_1") (pintype "passive"))
      (node (ref "U3") (pin "1") (pinfunction "Y1_1") (pintype "input"))
      (node (ref "U4") (pin "8") (pinfunction "X2_8") (pintype "input"))
    )
    (net (code "56") (name "Net-(U4-W)") (class "Default")
      (node (ref "J4") (pin "1") (pinfunction "1_1") (pintype "passive"))
      (node (ref "R9") (pin "1") (pinfunction "1_1") (pintype "passive"))
      (node (ref "U4") (pin "5") (pinfunction "W_5") (pintype "output"))
    )
    (net (code "57") (name "Net-(U4-Y1)") (class "Default")
      (node (ref "J2") (pin "1") (pinfunction "1_1") (pintype "passive"))
      (node (ref "JP3") (pin "1") (pinfunction "1_1") (pintype "passive"))
      (node (ref "U4") (pin "1") (pinfunction "Y1_1") (pintype "input"))
    )
    (net (code "58") (name "Net-(U5-IN+)") (class "Default")
      (node (ref "C2") (pin "1") (pinfunction "1_1") (pintype "passive"))
      (node (ref "R8") (pin "2") (pinfunction "2_2") (pintype "passive"))
      (node (ref "U5") (pin "3") (pinfunction "IN+_3") (pintype "input"))
    )
    (net (code "59") (name "Net-(U5-IN-)") (class "Default")
      (node (ref "C1") (pin "2") (pinfunction "2_2") (pintype "passive"))
      (node (ref "J5") (pin "1") (pinfunction "1_1") (pintype "passive"))
      (node (ref "R13") (pin "1") (pinfunction "1_1") (pintype "passive"))
      (node (ref "U5") (pin "2") (pinfunction "IN-_2") (pintype "input"))
      (node (ref "U5") (pin "6") (pinfunction "OUT_6") (pintype "output"))
    )
    (net (code "60") (name "Net-(U6-IN+)") (class "Default")
      (node (ref "C4") (pin "1") (pinfunction "1_1") (pintype "passive"))
      (node (ref "R10") (pin "2") (pinfunction "2_2") (pintype "passive"))
      (node (ref "U6") (pin "3") (pinfunction "IN+_3") (pintype "input"))
    )
    (net (code "61") (name "Net-(U6-IN-)") (class "Default")
      (node (ref "C3") (pin "2") (pinfunction "2_2") (pintype "passive"))
      (node (ref "J6") (pin "1") (pinfunction "1_1") (pintype "passive"))
      (node (ref "R20") (pin "1") (pinfunction "1_1") (pintype "passive"))
      (node (ref "U6") (pin "2") (pinfunction "IN-_2") (pintype "input"))
      (node (ref "U6") (pin "6") (pinfunction "OUT_6") (pintype "output"))
    )
    (net (code "62") (name "Net-(U7-IN+)") (class "Default")
      (node (ref "R11") (pin "1") (pinfunction "1_1") (pintype "passive"))
      (node (ref "R12") (pin "2") (pinfunction "2_2") (pintype "passive"))
      (node (ref "U7") (pin "3") (pinfunction "IN+_3") (pintype "input"))
    )
    (net (code "63") (name "Net-(U7-IN-)") (class "Default")
      (node (ref "J7") (pin "1") (pinfunction "1_1") (pintype "passive"))
      (node (ref "R14") (pin "1") (pinfunction "1_1") (pintype "passive"))
      (node (ref "U7") (pin "2") (pinfunction "IN-_2") (pintype "input"))
      (node (ref "U7") (pin "6") (pinfunction "OUT_6") (pintype "output"))
    )
    (net (code "64") (name "Net-(U8-IN+)") (class "Default")
      (node (ref "R13") (pin "2") (pinfunction "2_2") (pintype "passive"))
      (node (ref "R14") (pin "2") (pinfunction "2_2") (pintype "passive"))
      (node (ref "R15") (pin "2") (pinfunction "2_2") (pintype "passive"))
      (node (ref "U8") (pin "3") (pinfunction "IN+_3") (pintype "input"))
    )
    (net (code "65") (name "Net-(U8-IN-)") (class "Default")
      (node (ref "R16") (pin "2") (pinfunction "2_2") (pintype "passive"))
      (node (ref "R17") (pin "1") (pinfunction "1_1") (pintype "passive"))
      (node (ref "U8") (pin "2") (pinfunction "IN-_2") (pintype "input"))
    )
    (net (code "66") (name "Net-(U9-IN+)") (class "Default")
      (node (ref "R18") (pin "1") (pinfunction "1_1") (pintype "passive"))
      (node (ref "R19") (pin "2") (pinfunction "2_2") (pintype "passive"))
      (node (ref "U9") (pin "3") (pinfunction "IN+_3") (pintype "input"))
    )
    (net (code "67") (name "Net-(U9-IN-)") (class "Default")
      (node (ref "J8") (pin "1") (pinfunction "1_1") (pintype "passive"))
      (node (ref "R21") (pin "1") (pinfunction "1_1") (pintype "passive"))
      (node (ref "U9") (pin "2") (pinfunction "IN-_2") (pintype "input"))
      (node (ref "U9") (pin "6") (pinfunction "OUT_6") (pintype "output"))
    )
    (net (code "68") (name "Net-(U10-IN+)") (class "Default")
      (node (ref "R20") (pin "2") (pinfunction "2_2") (pintype "passive"))
      (node (ref "R21") (pin "2") (pinfunction "2_2") (pintype "passive"))
      (node (ref "R22") (pin "2") (pinfunction "2_2") (pintype "passive"))
      (node (ref "U10") (pin "3") (pinfunction "IN+_3") (pintype "input"))
    )
    (net (code "69") (name "Net-(U10-IN-)") (class "Default")
      (node (ref "R23") (pin "2") (pinfunction "2_2") (pintype "passive"))
      (node (ref "R24") (pin "1") (pinfunction "1_1") (pintype "passive"))
      (node (ref "U10") (pin "2") (pinfunction "IN-_2") (pintype "input"))
    )
    (net (code "70") (name "VCC") (class "Default")
      (node (ref "P3") (pin "11") (pinfunction "11_11") (pintype "passive"))
      (node (ref "P5") (pin "2") (pinfunction "2_2") (pintype "passive"))
      (node (ref "P5") (pin "7") (pinfunction "7_7") (pintype "passive"))
      (node (ref "P5") (pin "8") (pinfunction "8_8") (pintype "passive"))
      (node (ref "P6") (pin "1") (pinfunction "1_1") (pintype "passive"))
    )
    (net (code "71") (name "unconnected-(I1-Pad2)") (class "Default")
      (node (ref "I1") (pin "2") (pinfunction "2_2") (pintype "passive"))
    )
    (net (code "72") (name "unconnected-(I1-Pad3)") (class "Default")
      (node (ref "I1") (pin "3") (pinfunction "3_3") (pintype "passive"))
    )
    (net (code "73") (name "unconnected-(I1-Pad4)") (class "Default")
      (node (ref "I1") (pin "4") (pinfunction "4_4") (pintype "passive"))
    )
    (net (code "74") (name "unconnected-(I2-Pad2)") (class "Default")
      (node (ref "I2") (pin "2") (pinfunction "2_2") (pintype "passive"))
    )
    (net (code "75") (name "unconnected-(I2-Pad3)") (class "Default")
      (node (ref "I2") (pin "3") (pinfunction "3_3") (pintype "passive"))
    )
    (net (code "76") (name "unconnected-(I2-Pad4)") (class "Default")
      (node (ref "I2") (pin "4") (pinfunction "4_4") (pintype "passive"))
    )
    (net (code "77") (name "unconnected-(JP1-Pad1)") (class "Default")
      (node (ref "JP1") (pin "1") (pinfunction "1_1") (pintype "passive"))
    )
    (net (code "78") (name "unconnected-(JP1-Pad2)") (class "Default")
      (node (ref "JP1") (pin "2") (pinfunction "2_2") (pintype "passive"))
    )
    (net (code "79") (name "unconnected-(P3-Pad1)") (class "Default")
      (node (ref "P3") (pin "1") (pinfunction "1_1") (pintype "passive"))
    )
    (net (code "80") (name "unconnected-(P3-Pad5)") (class "Default")
      (node (ref "P3") (pin "5") (pinfunction "5_5") (pintype "passive"))
    )
    (net (code "81") (name "unconnected-(P4-Pad13)") (class "Default")
      (node (ref "P4") (pin "13") (pinfunction "13_13") (pintype "passive"))
    )
    (net (code "82") (name "unconnected-(P4-Pad15)") (class "Default")
      (node (ref "P4") (pin "15") (pinfunction "15_15") (pintype "passive"))
    )
    (net (code "83") (name "unconnected-(P4-Pad19)") (class "Default")
      (node (ref "P4") (pin "19") (pinfunction "19_19") (pintype "passive"))
    )
    (net (code "84") (name "unconnected-(P6-Pad6)") (class "Default")
      (node (ref "P6") (pin "6") (pinfunction "6_6") (pintype "passive"))
    )
    (net (code "85") (name "unconnected-(P6-Pad9)") (class "Default")
      (node (ref "P6") (pin "9") (pinfunction "9_9") (pintype "passive"))
    )
    (net (code "86") (name "unconnected-(P6-Pad10)") (class "Default")
      (node (ref "P6") (pin "10") (pinfunction "10_10") (pintype "passive"))
    )
    (net (code "87") (name "unconnected-(P7-3V3-Pad19)") (class "Default")
      (node (ref "P7") (pin "19") (pinfunction "3V3_19") (pintype "passive"))
    )
    (net (code "88") (name "unconnected-(P7-3V3-Pad21)") (class "Default")
      (node (ref "P7") (pin "21") (pinfunction "3V3_21") (pintype "passive"))
    )
    (net (code "89") (name "unconnected-(P7-FSK-Pad22)") (class "Default")
      (node (ref "P7") (pin "22") (pinfunction "FSK_22") (pintype "passive"))
    )
    (net (code "90") (name "unconnected-(P7-OSK-Pad20)") (class "Default")
      (node (ref "P7") (pin "20") (pinfunction "OSK_20") (pintype "passive"))
    )
    (net (code "91") (name "unconnected-(SMA1-Pad2)") (class "Default")
      (node (ref "SMA1") (pin "2") (pinfunction "2_2") (pintype "passive"))
    )
    (net (code "92") (name "unconnected-(SMA1-Pad3)") (class "Default")
      (node (ref "SMA1") (pin "3") (pinfunction "3_3") (pintype "passive"))
    )
    (net (code "93") (name "unconnected-(SMA1-Pad4)") (class "Default")
      (node (ref "SMA1") (pin "4") (pinfunction "4_4") (pintype "passive"))
    )
    (net (code "94") (name "unconnected-(SMA1-Pad5)") (class "Default")
      (node (ref "SMA1") (pin "5") (pinfunction "5_5") (pintype "passive"))
    )
    (net (code "95") (name "unconnected-(SMA2-Pad2)") (class "Default")
      (node (ref "SMA2") (pin "2") (pinfunction "2_2") (pintype "passive"))
    )
    (net (code "96") (name "unconnected-(SMA2-Pad3)") (class "Default")
      (node (ref "SMA2") (pin "3") (pinfunction "3_3") (pintype "passive"))
    )
    (net (code "97") (name "unconnected-(SMA2-Pad4)") (class "Default")
      (node (ref "SMA2") (pin "4") (pinfunction "4_4") (pintype "passive"))
    )
    (net (code "98") (name "unconnected-(SMA2-Pad5)") (class "Default")
      (node (ref "SMA2") (pin "5") (pinfunction "5_5") (pintype "passive"))
    )
    (net (code "99") (name "unconnected-(U1-NC-Pad5)") (class "Default")
      (node (ref "U1") (pin "5") (pinfunction "NC_5") (pintype "passive"))
    )
    (net (code "100") (name "unconnected-(U1-VOSTRIM-Pad1)") (class "Default")
      (node (ref "U1") (pin "1") (pinfunction "VOSTRIM_1") (pintype "passive"))
    )
    (net (code "101") (name "unconnected-(U1-VOSTRIM-Pad8)") (class "Default")
      (node (ref "U1") (pin "8") (pinfunction "VOSTRIM_8") (pintype "passive"))
    )
    (net (code "102") (name "unconnected-(U2-NC-Pad5)") (class "Default")
      (node (ref "U2") (pin "5") (pinfunction "NC_5") (pintype "passive"))
    )
    (net (code "103") (name "unconnected-(U2-VOSTRIM-Pad1)") (class "Default")
      (node (ref "U2") (pin "1") (pinfunction "VOSTRIM_1") (pintype "passive"))
    )
    (net (code "104") (name "unconnected-(U2-VOSTRIM-Pad8)") (class "Default")
      (node (ref "U2") (pin "8") (pinfunction "VOSTRIM_8") (pintype "passive"))
    )
    (net (code "105") (name "unconnected-(U5-NC-Pad5)") (class "Default")
      (node (ref "U5") (pin "5") (pinfunction "NC_5") (pintype "passive"))
    )
    (net (code "106") (name "unconnected-(U5-VOSTRIM-Pad1)") (class "Default")
      (node (ref "U5") (pin "1") (pinfunction "VOSTRIM_1") (pintype "passive"))
    )
    (net (code "107") (name "unconnected-(U5-VOSTRIM-Pad8)") (class "Default")
      (node (ref "U5") (pin "8") (pinfunction "VOSTRIM_8") (pintype "passive"))
    )
    (net (code "108") (name "unconnected-(U6-NC-Pad5)") (class "Default")
      (node (ref "U6") (pin "5") (pinfunction "NC_5") (pintype "passive"))
    )
    (net (code "109") (name "unconnected-(U6-VOSTRIM-Pad1)") (class "Default")
      (node (ref "U6") (pin "1") (pinfunction "VOSTRIM_1") (pintype "passive"))
    )
    (net (code "110") (name "unconnected-(U6-VOSTRIM-Pad8)") (class "Default")
      (node (ref "U6") (pin "8") (pinfunction "VOSTRIM_8") (pintype "passive"))
    )
    (net (code "111") (name "unconnected-(U7-NC-Pad5)") (class "Default")
      (node (ref "U7") (pin "5") (pinfunction "NC_5") (pintype "passive"))
    )
    (net (code "112") (name "unconnected-(U7-VOSTRIM-Pad1)") (class "Default")
      (node (ref "U7") (pin "1") (pinfunction "VOSTRIM_1") (pintype "passive"))
    )
    (net (code "113") (name "unconnected-(U7-VOSTRIM-Pad8)") (class "Default")
      (node (ref "U7") (pin "8") (pinfunction "VOSTRIM_8") (pintype "passive"))
    )
    (net (code "114") (name "unconnected-(U8-NC-Pad5)") (class "Default")
      (node (ref "U8") (pin "5") (pinfunction "NC_5") (pintype "passive"))
    )
    (net (code "115") (name "unconnected-(U8-VOSTRIM-Pad1)") (class "Default")
      (node (ref "U8") (pin "1") (pinfunction "VOSTRIM_1") (pintype "passive"))
    )
    (net (code "116") (name "unconnected-(U8-VOSTRIM-Pad8)") (class "Default")
      (node (ref "U8") (pin "8") (pinfunction "VOSTRIM_8") (pintype "passive"))
    )
    (net (code "117") (name "unconnected-(U9-NC-Pad5)") (class "Default")
      (node (ref "U9") (pin "5") (pinfunction "NC_5") (pintype "passive"))
    )
    (net (code "118") (name "unconnected-(U9-VOSTRIM-Pad1)") (class "Default")
      (node (ref "U9") (pin "1") (pinfunction "VOSTRIM_1") (pintype "passive"))
    )
    (net (code "119") (name "unconnected-(U9-VOSTRIM-Pad8)") (class "Default")
      (node (ref "U9") (pin "8") (pinfunction "VOSTRIM_8") (pintype "passive"))
    )
    (net (code "120") (name "unconnected-(U10-NC-Pad5)") (class "Default")
      (node (ref "U10") (pin "5") (pinfunction "NC_5") (pintype "passive"))
    )
    (net (code "121") (name "unconnected-(U10-VOSTRIM-Pad1)") (class "Default")
      (node (ref "U10") (pin "1") (pinfunction "VOSTRIM_1") (pintype "passive"))
    )
    (net (code "122") (name "unconnected-(U10-VOSTRIM-Pad8)") (class "Default")
      (node (ref "U10") (pin "8") (pinfunction "VOSTRIM_8") (pintype "passive"))
    )
  )
)
